# SCH_RFID-ARDUINO-FABLAB-BG-v2_2024-03-10.net
KiCad netlist of a schematic drawn in EasyEDA
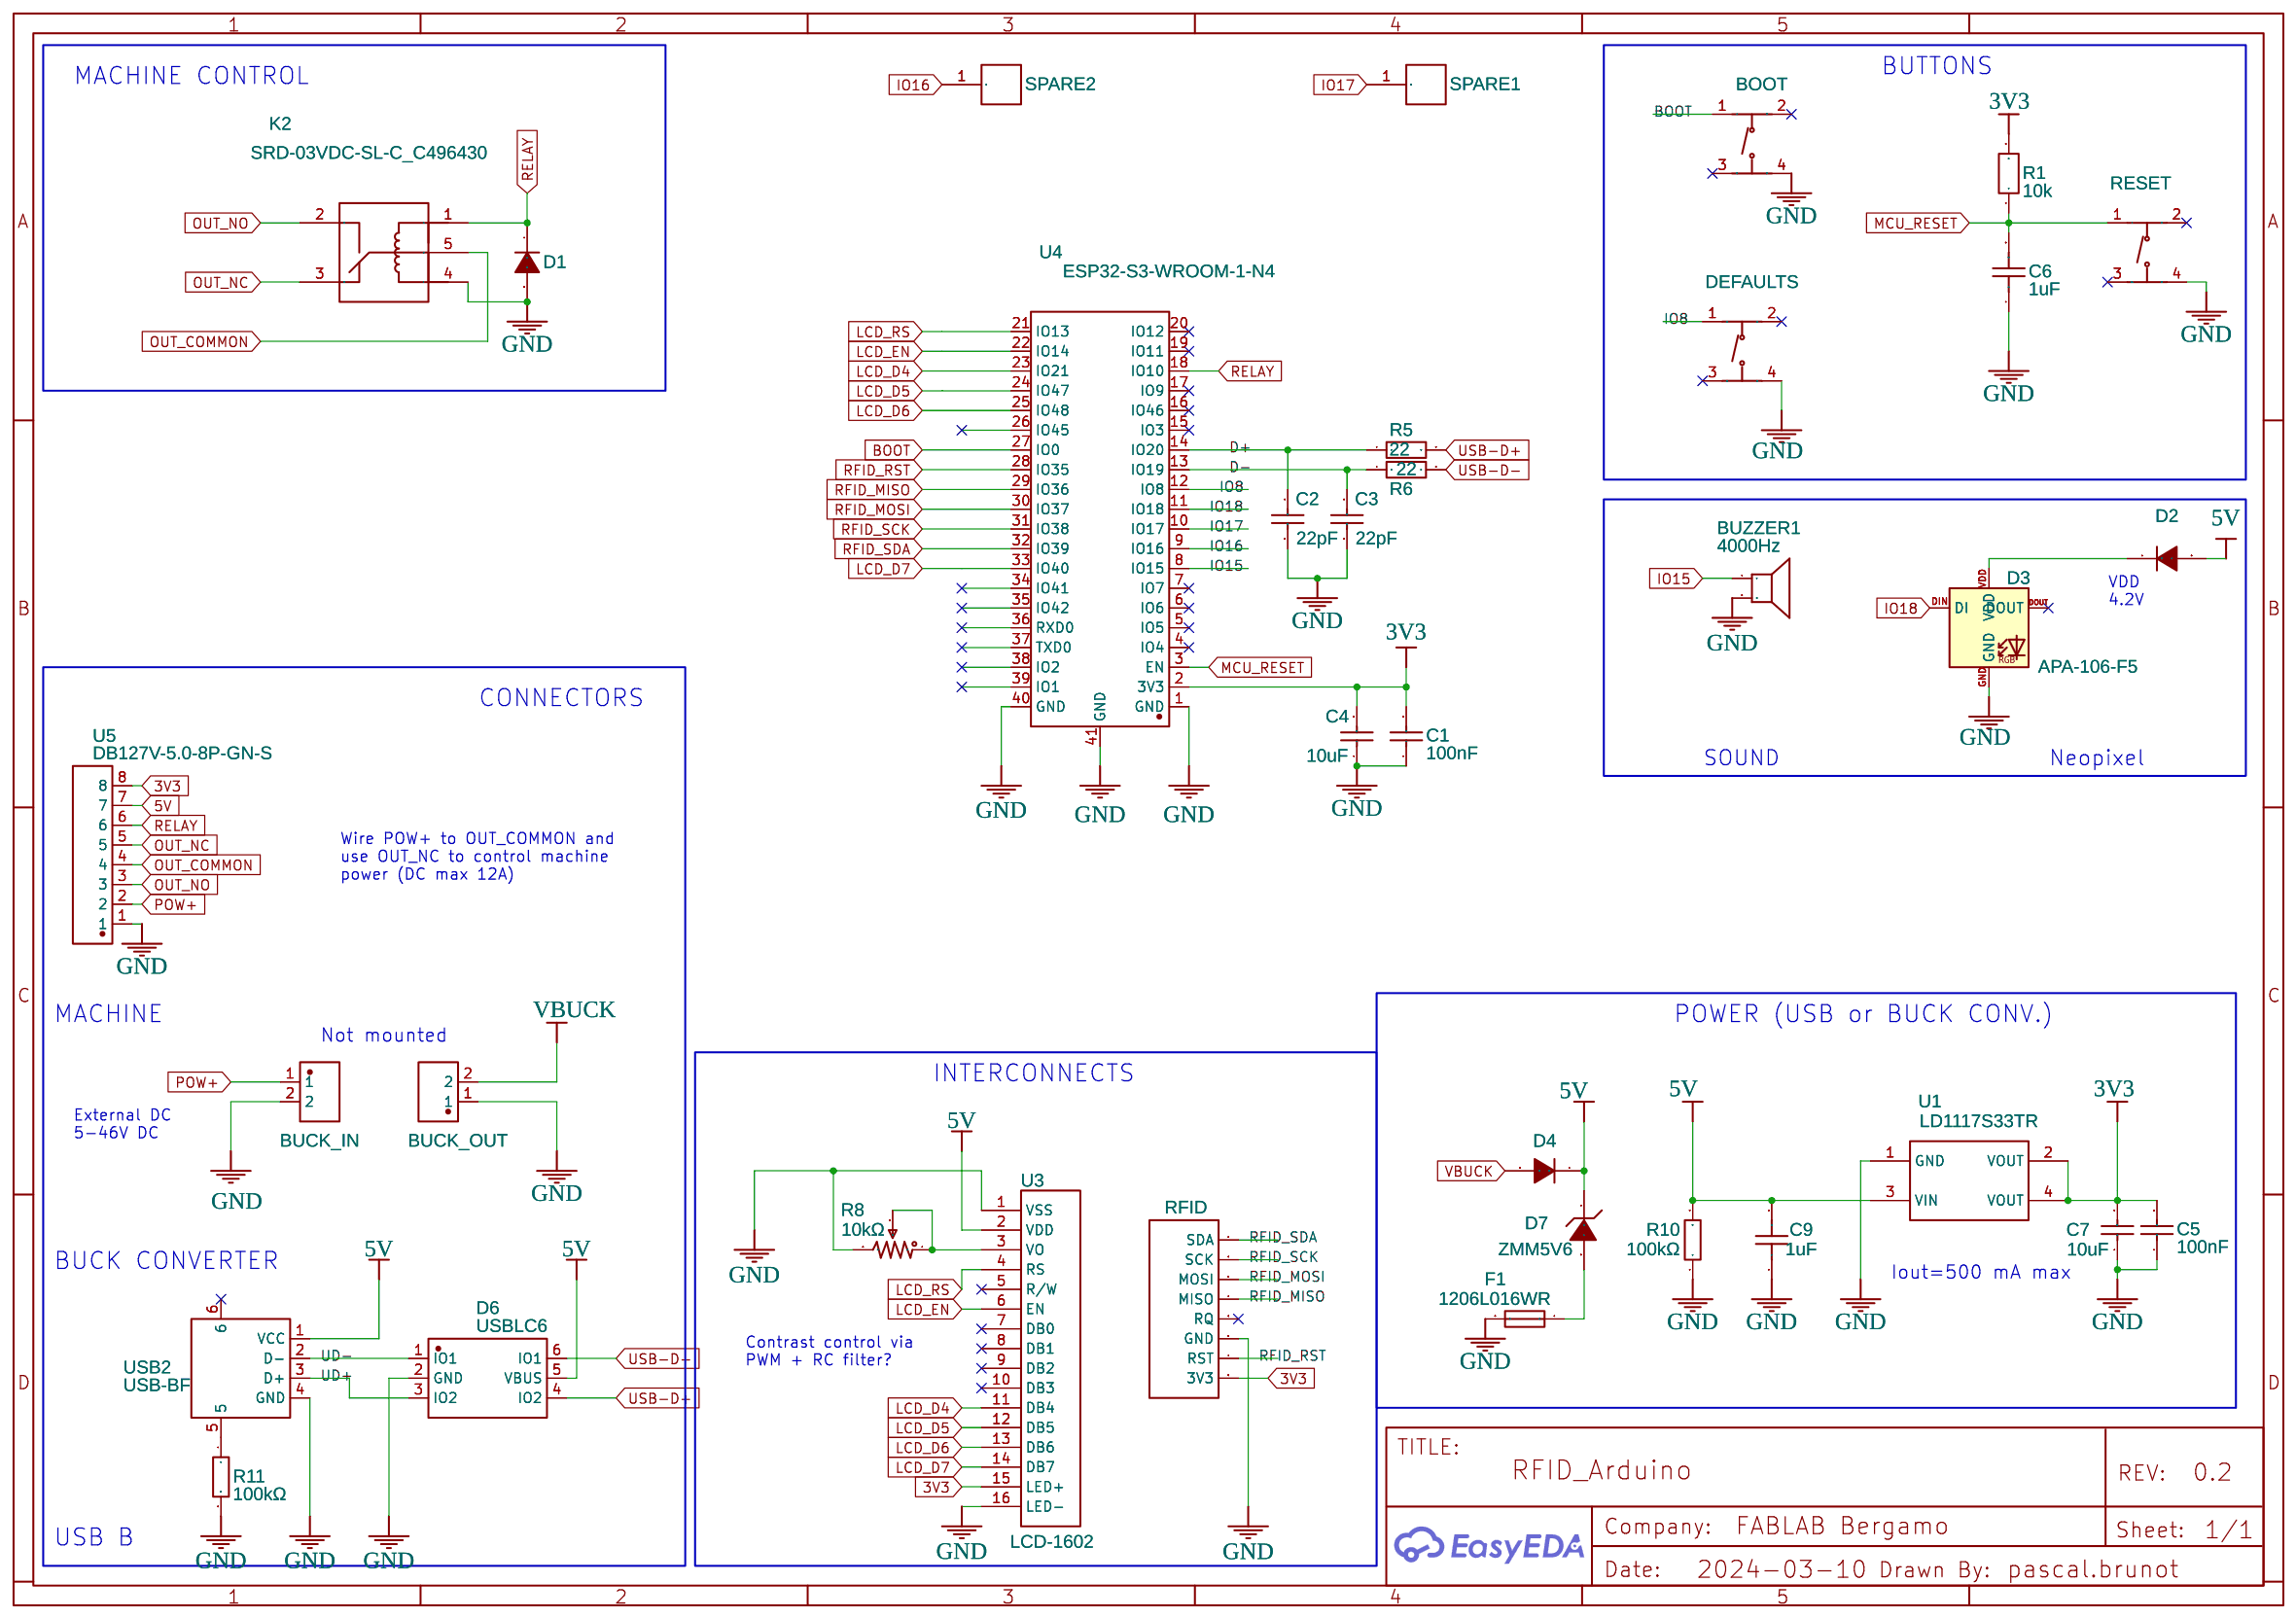
[diagram p0: schematic sheet]

(export (version "E")
  (design (tool "Eeschema 10.0.6"))
  (components
    (comp (ref "BOOT")
      (value "TS-1187A-B-A-B")
      (fields (field (name "Manufacturer") "XKB Connectivity(中国星坤)"))
      (libsource (lib "") (part "TS-1187A-B-A-B"))
    )
    (comp (ref "BUCK_IN")
      (value "KF128L-3.81-2P")
      (fields (field (name "Manufacturer") "KEFA(科发)"))
      (libsource (lib "") (part "KF128L-3.81-2P_1"))
    )
    (comp (ref "BUCK_OUT")
      (value "KF128L-3.81-2P")
      (fields (field (name "Manufacturer") "KEFA(科发)"))
      (libsource (lib "") (part "KF128L-3.81-2P"))
    )
    (comp (ref "BUZZER1")
      (value "4000Hz")
      (fields (field (name "Manufacturer Part") "SFN-12055PA6.5") (field (name "Manufacturer") "S&S(海旭)"))
      (libsource (lib "") (part "SFN-12055PA6.5"))
    )
    (comp (ref "C1")
      (value "100nF")
      (fields
        (field (name "Manufacturer Part") "CL21B104KCFNNNE")
        (field (name "Manufacturer") "SAMSUNG(三星)")
      )
      (libsource (lib "") (part "CL21B104KCFNNNE"))
    )
    (comp (ref "C2")
      (value "22pF")
      (fields (field (name "Manufacturer Part") "0402CG220J500NT") (field (name "Manufacturer") "FH(风华)"))
      (libsource (lib "") (part "0402CG220J500NT"))
    )
    (comp (ref "C3")
      (value "22pF")
      (fields (field (name "Manufacturer Part") "0402CG220J500NT") (field (name "Manufacturer") "FH(风华)"))
      (libsource (lib "") (part "0402CG220J500NT"))
    )
    (comp (ref "C4")
      (value "10uF")
      (fields
        (field (name "Manufacturer Part") "CL31A106KBHNNNE")
        (field (name "Manufacturer") "SAMSUNG(三星)")
      )
      (libsource (lib "") (part "CL31A106KBHNNNE"))
    )
    (comp (ref "C5")
      (value "100nF")
      (fields
        (field (name "Manufacturer Part") "CL21B104KCFNNNE")
        (field (name "Manufacturer") "SAMSUNG(三星)")
      )
      (libsource (lib "") (part "CL21B104KCFNNNE"))
    )
    (comp (ref "C6")
      (value "1uF")
      (fields
        (field (name "Manufacturer Part") "CL31B105KBHNNNE")
        (field (name "Manufacturer") "SAMSUNG(三星)")
      )
      (libsource (lib "") (part "CL31B105KBHNNNE"))
    )
    (comp (ref "C7")
      (value "10uF")
      (fields
        (field (name "Manufacturer Part") "CL31A106KBHNNNE")
        (field (name "Manufacturer") "SAMSUNG(三星)")
      )
      (libsource (lib "") (part "CL31A106KBHNNNE"))
    )
    (comp (ref "C9")
      (value "1uF")
      (fields
        (field (name "Manufacturer Part") "CL31B105KBHNNNE")
        (field (name "Manufacturer") "SAMSUNG(三星)")
      )
      (libsource (lib "") (part "CL31B105KBHNNNE"))
    )
    (comp (ref "D1")
      (value "SM4007PL")
      (fields (field (name "Manufacturer") "MDD"))
      (libsource (lib "") (part "SM4007PL_1"))
    )
    (comp (ref "D2")
      (value "SM4007PL")
      (fields (field (name "Manufacturer") "MDD"))
      (libsource (lib "") (part "SM4007PL"))
    )
    (comp (ref "D3") (value "APA-106-F5") (libsource (lib "") (part "APA-106-F5 COPY")))
    (comp (ref "D4")
      (value "SM4007PL")
      (fields (field (name "Manufacturer") "MDD"))
      (libsource (lib "") (part "SM4007PL_2"))
    )
    (comp (ref "D6")
      (value "USBLC6")
      (fields
        (field (name "Manufacturer Part") "USBLC6-2SC6")
        (field (name "Manufacturer") "TECH PUBLIC(台舟)")
      )
      (libsource (lib "") (part "USBLC6-2SC6_C2827654"))
    )
    (comp (ref "D7")
      (value "ZMM5V6")
      (fields (field (name "Manufacturer Part") "ZMM5V6-M") (field (name "Manufacturer") "ST(先科)"))
      (libsource (lib "") (part "ZMM5V6"))
    )
    (comp (ref "DEFAULTS")
      (value "TS-1187A-B-A-B")
      (fields (field (name "Manufacturer") "XKB Connectivity(中国星坤)"))
      (libsource (lib "") (part "TS-1187A-B-A-B_1"))
    )
    (comp (ref "F1")
      (value "1206L016WR")
      (fields (field (name "Manufacturer") "Littelfuse(美国力特)"))
      (libsource (lib "") (part "1206L016WR"))
    )
    (comp (ref "K2")
      (value "SRD-03VDC-SL-C_C496430")
      (fields (field (name "Manufacturer Part") "SRD-03VDC-SL-C") (field (name "Manufacturer") "松乐"))
      (libsource (lib "") (part "SRD-03VDC-SL-C_C496430"))
    )
    (comp (ref "P1")
      (value "RFID")
      (fields
        (field (name "Manufacturer Part") "Female headerHDR1X8-2.54")
        (field (name "Manufacturer") "BOOMELE")
      )
      (libsource (lib "") (part "RFID2"))
    )
    (comp (ref "R1")
      (value "10k")
      (fields
        (field (name "Manufacturer Part") "0805W8F1002T5E")
        (field (name "Manufacturer") "UNI-ROYAL(厚声)")
      )
      (libsource (lib "") (part "R_0603_EU"))
    )
    (comp (ref "R5")
      (value "22")
      (fields
        (field (name "Manufacturer Part") "0603WAF220JT5E")
        (field (name "Manufacturer") "UNI-ROYAL(厚声)")
      )
      (libsource (lib "") (part "0603WAF220JT5E"))
    )
    (comp (ref "R6")
      (value "22")
      (fields
        (field (name "Manufacturer Part") "0603WAF220JT5E")
        (field (name "Manufacturer") "UNI-ROYAL(厚声)")
      )
      (libsource (lib "") (part "0603WAF220JT5E"))
    )
    (comp (ref "R8")
      (value "10kΩ")
      (fields (field (name "Manufacturer Part") "TC33X-2-103E") (field (name "Manufacturer") "BOURNS"))
      (libsource (lib "") (part "TC33X-2-103E"))
    )
    (comp (ref "R10")
      (value "100kΩ")
      (fields
        (field (name "Manufacturer Part") "0805W8F1003T5E")
        (field (name "Manufacturer") "UNI-ROYAL(厚声)")
      )
      (libsource (lib "") (part "0805W8F1003T5E_C149504_1"))
    )
    (comp (ref "R11")
      (value "100kΩ")
      (fields
        (field (name "Manufacturer Part") "0805W8F1003T5E")
        (field (name "Manufacturer") "UNI-ROYAL(厚声)")
      )
      (libsource (lib "") (part "0805W8F1003T5E_C149504"))
    )
    (comp (ref "RESET")
      (value "TS-1187A-B-A-B")
      (fields (field (name "Manufacturer") "XKB Connectivity(中国星坤)"))
      (libsource (lib "") (part "TS-1187A-B-A-B_2"))
    )
    (comp (ref "SPARE1")
      (value "0577-0-43-80-21-27-10-0")
      (libsource (lib "") (part "0577-0-43-80-21-27-10-0"))
    )
    (comp (ref "SPARE2")
      (value "0577-0-43-80-21-27-10-0")
      (libsource (lib "") (part "0577-0-43-80-21-27-10-0"))
    )
    (comp (ref "U1")
      (value "LD1117S33TR")
      (fields (field (name "Manufacturer") "ST(意法半导体)"))
      (libsource (lib "") (part "LD1117S33TR"))
    )
    (comp (ref "U3")
      (value "LCD-1602")
      (fields (field (name "Manufacturer Part") "?"))
      (libsource (lib "") (part "Unknown_540_-60"))
    )
    (comp (ref "U4")
      (value "ESP32-S3-WROOM-1-N4")
      (fields (field (name "Manufacturer") "ESPRESSIF(乐鑫)"))
      (libsource (lib "") (part "ESP32-S3-WROOM-1-N4"))
    )
    (comp (ref "U5")
      (value "DB127V-5.0-8P-GN-S")
      (fields (field (name "Manufacturer") "DORABO(地博电气)"))
      (libsource (lib "") (part "DB127V-5.0-8P-GN-S"))
    )
    (comp (ref "USB2")
      (value "USB-BF")
      (fields (field (name "Manufacturer Part") "670688000") (field (name "Manufacturer") "MOLEX"))
      (libsource (lib "") (part "USB-BF"))
    )
  )
  (nets
    (net (code "1") (name "/D+") (class "Default")
      (node (ref "C2") (pin "2") (pinfunction "2_2") (pintype "input"))
      (node (ref "R5") (pin "1") (pinfunction "1_1") (pintype "input"))
      (node (ref "U4") (pin "14") (pinfunction "IO20_14") (pintype "unspecified"))
    )
    (net (code "2") (name "/D-") (class "Default")
      (node (ref "C3") (pin "2") (pinfunction "2_2") (pintype "input"))
      (node (ref "R6") (pin "1") (pinfunction "1_1") (pintype "input"))
      (node (ref "U4") (pin "13") (pinfunction "IO19_13") (pintype "unspecified"))
    )
    (net (code "3") (name "/IO8") (class "Default")
      (node (ref "DEFAULTS") (pin "1") (pinfunction "A_1") (pintype "unspecified"))
      (node (ref "U4") (pin "12") (pinfunction "IO8_12") (pintype "unspecified"))
    )
    (net (code "4") (name "/UD+") (class "Default")
      (node (ref "D6") (pin "3") (pinfunction "IO2_3") (pintype "unspecified"))
      (node (ref "USB2") (pin "3") (pinfunction "D+_3") (pintype "unspecified"))
    )
    (net (code "5") (name "/UD-") (class "Default")
      (node (ref "D6") (pin "1") (pinfunction "IO1_1") (pintype "unspecified"))
      (node (ref "USB2") (pin "2") (pinfunction "D-_2") (pintype "unspecified"))
    )
    (net (code "6") (name "3V3") (class "Default")
      (node (ref "C1") (pin "2") (pinfunction "2_2") (pintype "input"))
      (node (ref "C4") (pin "2") (pinfunction "2_2") (pintype "input"))
      (node (ref "C5") (pin "2") (pinfunction "2_2") (pintype "input"))
      (node (ref "C7") (pin "2") (pinfunction "2_2") (pintype "input"))
      (node (ref "P1") (pin "8") (pinfunction "3V3_8") (pintype "input"))
      (node (ref "R1") (pin "2") (pinfunction "2_2") (pintype "unspecified"))
      (node (ref "U1") (pin "2") (pinfunction "VOUT_2") (pintype "unspecified"))
      (node (ref "U1") (pin "4") (pinfunction "VOUT_4") (pintype "unspecified"))
      (node (ref "U3") (pin "15") (pinfunction "LED+_15") (pintype "unspecified"))
      (node (ref "U4") (pin "2") (pinfunction "3V3_2") (pintype "unspecified"))
      (node (ref "U5") (pin "8") (pinfunction "8_8") (pintype "unspecified"))
    )
    (net (code "7") (name "5V") (class "Default")
      (node (ref "C9") (pin "2") (pinfunction "2_2") (pintype "unspecified"))
      (node (ref "D2") (pin "2") (pinfunction "A_2") (pintype "unspecified"))
      (node (ref "D4") (pin "1") (pinfunction "C_1") (pintype "unspecified"))
      (node (ref "D6") (pin "5") (pinfunction "VBUS_5") (pintype "unspecified"))
      (node (ref "D7") (pin "1") (pinfunction "C_1") (pintype "unspecified"))
      (node (ref "R10") (pin "2") (pinfunction "2_2") (pintype "unspecified"))
      (node (ref "U1") (pin "3") (pinfunction "VIN_3") (pintype "unspecified"))
      (node (ref "U3") (pin "2") (pinfunction "VDD_2") (pintype "unspecified"))
      (node (ref "U5") (pin "7") (pinfunction "7_7") (pintype "unspecified"))
      (node (ref "USB2") (pin "1") (pinfunction "VCC_1") (pintype "unspecified"))
    )
    (net (code "8") (name "BOOT") (class "Default")
      (node (ref "BOOT") (pin "1") (pinfunction "A_1") (pintype "unspecified"))
      (node (ref "U4") (pin "27") (pinfunction "IO0_27") (pintype "unspecified"))
    )
    (net (code "9") (name "GND") (class "Default")
      (node (ref "BOOT") (pin "4") (pinfunction "D_4") (pintype "unspecified"))
      (node (ref "BUCK_IN") (pin "2") (pinfunction "2_2") (pintype "unspecified"))
      (node (ref "BUCK_OUT") (pin "1") (pinfunction "1_1") (pintype "unspecified"))
      (node (ref "BUZZER1") (pin "2") (pinfunction "2_2") (pintype "unspecified"))
      (node (ref "C1") (pin "1") (pinfunction "1_1") (pintype "input"))
      (node (ref "C2") (pin "1") (pinfunction "1_1") (pintype "input"))
      (node (ref "C3") (pin "1") (pinfunction "1_1") (pintype "input"))
      (node (ref "C4") (pin "1") (pinfunction "1_1") (pintype "input"))
      (node (ref "C5") (pin "1") (pinfunction "1_1") (pintype "input"))
      (node (ref "C6") (pin "1") (pinfunction "1_1") (pintype "unspecified"))
      (node (ref "C7") (pin "1") (pinfunction "1_1") (pintype "input"))
      (node (ref "C9") (pin "1") (pinfunction "1_1") (pintype "unspecified"))
      (node (ref "D1") (pin "2") (pinfunction "A_2") (pintype "unspecified"))
      (node (ref "D3") (pin "GND") (pinfunction "GND_GND") (pintype "bidirectional"))
      (node (ref "D6") (pin "2") (pinfunction "GND_2") (pintype "unspecified"))
      (node (ref "DEFAULTS") (pin "4") (pinfunction "D_4") (pintype "unspecified"))
      (node (ref "F1") (pin "2") (pinfunction "2_2") (pintype "unspecified"))
      (node (ref "K2") (pin "4") (pinfunction "4_4") (pintype "unspecified"))
      (node (ref "P1") (pin "6") (pinfunction "GND_6") (pintype "input"))
      (node (ref "R10") (pin "1") (pinfunction "1_1") (pintype "unspecified"))
      (node (ref "R11") (pin "2") (pinfunction "2_2") (pintype "unspecified"))
      (node (ref "R8") (pin "3") (pinfunction "3_3") (pintype "unspecified"))
      (node (ref "RESET") (pin "4") (pinfunction "D_4") (pintype "unspecified"))
      (node (ref "U1") (pin "1") (pinfunction "GND_1") (pintype "unspecified"))
      (node (ref "U3") (pin "1") (pinfunction "VSS_1") (pintype "unspecified"))
      (node (ref "U3") (pin "16") (pinfunction "LED-_16") (pintype "unspecified"))
      (node (ref "U4") (pin "1") (pinfunction "GND_1") (pintype "unspecified"))
      (node (ref "U4") (pin "40") (pinfunction "GND_40") (pintype "unspecified"))
      (node (ref "U4") (pin "41") (pinfunction "GND_41") (pintype "unspecified"))
      (node (ref "U5") (pin "1") (pinfunction "1_1") (pintype "unspecified"))
      (node (ref "USB2") (pin "4") (pinfunction "GND_4") (pintype "unspecified"))
    )
    (net (code "10") (name "IO15") (class "Default")
      (node (ref "BUZZER1") (pin "1") (pinfunction "1_1") (pintype "unspecified"))
      (node (ref "U4") (pin "8") (pinfunction "IO15_8") (pintype "unspecified"))
    )
    (net (code "11") (name "IO16") (class "Default")
      (node (ref "SPARE2") (pin "1") (pinfunction "1_1") (pintype "unspecified"))
      (node (ref "U4") (pin "9") (pinfunction "IO16_9") (pintype "unspecified"))
    )
    (net (code "12") (name "IO17") (class "Default")
      (node (ref "SPARE1") (pin "1") (pinfunction "1_1") (pintype "unspecified"))
      (node (ref "U4") (pin "10") (pinfunction "IO17_10") (pintype "unspecified"))
    )
    (net (code "13") (name "IO18") (class "Default")
      (node (ref "D3") (pin "DIN") (pinfunction "DI_DIN") (pintype "input"))
      (node (ref "U4") (pin "11") (pinfunction "IO18_11") (pintype "unspecified"))
    )
    (net (code "14") (name "LCD_D4") (class "Default")
      (node (ref "U3") (pin "11") (pinfunction "DB4_11") (pintype "unspecified"))
      (node (ref "U4") (pin "23") (pinfunction "IO21_23") (pintype "unspecified"))
    )
    (net (code "15") (name "LCD_D5") (class "Default")
      (node (ref "U3") (pin "12") (pinfunction "DB5_12") (pintype "unspecified"))
      (node (ref "U4") (pin "24") (pinfunction "IO47_24") (pintype "unspecified"))
    )
    (net (code "16") (name "LCD_D6") (class "Default")
      (node (ref "U3") (pin "13") (pinfunction "DB6_13") (pintype "unspecified"))
      (node (ref "U4") (pin "25") (pinfunction "IO48_25") (pintype "unspecified"))
    )
    (net (code "17") (name "LCD_D7") (class "Default")
      (node (ref "U3") (pin "14") (pinfunction "DB7_14") (pintype "unspecified"))
      (node (ref "U4") (pin "33") (pinfunction "IO40_33") (pintype "unspecified"))
    )
    (net (code "18") (name "LCD_EN") (class "Default")
      (node (ref "U3") (pin "6") (pinfunction "EN_6") (pintype "unspecified"))
      (node (ref "U4") (pin "22") (pinfunction "IO14_22") (pintype "unspecified"))
    )
    (net (code "19") (name "LCD_RS") (class "Default")
      (node (ref "U3") (pin "4") (pinfunction "RS_4") (pintype "unspecified"))
      (node (ref "U4") (pin "21") (pinfunction "IO13_21") (pintype "unspecified"))
    )
    (net (code "20") (name "MCU_RESET") (class "Default")
      (node (ref "C6") (pin "2") (pinfunction "2_2") (pintype "unspecified"))
      (node (ref "R1") (pin "1") (pinfunction "1_1") (pintype "unspecified"))
      (node (ref "RESET") (pin "1") (pinfunction "A_1") (pintype "unspecified"))
      (node (ref "U4") (pin "3") (pinfunction "EN_3") (pintype "unspecified"))
    )
    (net (code "21") (name "Net-(D2-C)") (class "Default")
      (node (ref "D2") (pin "1") (pinfunction "C_1") (pintype "unspecified"))
      (node (ref "D3") (pin "VDD") (pinfunction "VDD_VDD") (pintype "bidirectional"))
    )
    (net (code "22") (name "Net-(D7-A)") (class "Default")
      (node (ref "D7") (pin "2") (pinfunction "A_2") (pintype "unspecified"))
      (node (ref "F1") (pin "1") (pinfunction "1_1") (pintype "unspecified"))
    )
    (net (code "23") (name "Net-(R11-Pad1)") (class "Default")
      (node (ref "R11") (pin "1") (pinfunction "1_1") (pintype "unspecified"))
      (node (ref "USB2") (pin "5") (pinfunction "5_5") (pintype "unspecified"))
    )
    (net (code "24") (name "Net-(U3-VO)") (class "Default")
      (node (ref "R8") (pin "1") (pinfunction "1_1") (pintype "unspecified"))
      (node (ref "R8") (pin "2") (pinfunction "2_2") (pintype "unspecified"))
      (node (ref "U3") (pin "3") (pinfunction "VO_3") (pintype "unspecified"))
    )
    (net (code "25") (name "OUT_COMMON") (class "Default")
      (node (ref "K2") (pin "5") (pinfunction "5_5") (pintype "unspecified"))
      (node (ref "U5") (pin "4") (pinfunction "4_4") (pintype "unspecified"))
    )
    (net (code "26") (name "OUT_NC") (class "Default")
      (node (ref "K2") (pin "3") (pinfunction "3_3") (pintype "unspecified"))
      (node (ref "U5") (pin "5") (pinfunction "5_5") (pintype "unspecified"))
    )
    (net (code "27") (name "OUT_NO") (class "Default")
      (node (ref "K2") (pin "2") (pinfunction "2_2") (pintype "unspecified"))
      (node (ref "U5") (pin "3") (pinfunction "3_3") (pintype "unspecified"))
    )
    (net (code "28") (name "POW+") (class "Default")
      (node (ref "BUCK_IN") (pin "1") (pinfunction "1_1") (pintype "unspecified"))
      (node (ref "U5") (pin "2") (pinfunction "2_2") (pintype "unspecified"))
    )
    (net (code "29") (name "RELAY") (class "Default")
      (node (ref "D1") (pin "1") (pinfunction "C_1") (pintype "unspecified"))
      (node (ref "K2") (pin "1") (pinfunction "1_1") (pintype "unspecified"))
      (node (ref "U4") (pin "18") (pinfunction "IO10_18") (pintype "unspecified"))
      (node (ref "U5") (pin "6") (pinfunction "6_6") (pintype "unspecified"))
    )
    (net (code "30") (name "RFID_MISO") (class "Default")
      (node (ref "P1") (pin "4") (pinfunction "MISO_4") (pintype "input"))
      (node (ref "U4") (pin "29") (pinfunction "IO36_29") (pintype "unspecified"))
    )
    (net (code "31") (name "RFID_MOSI") (class "Default")
      (node (ref "P1") (pin "3") (pinfunction "MOSI_3") (pintype "input"))
      (node (ref "U4") (pin "30") (pinfunction "IO37_30") (pintype "unspecified"))
    )
    (net (code "32") (name "RFID_RST") (class "Default")
      (node (ref "P1") (pin "7") (pinfunction "RST_7") (pintype "input"))
      (node (ref "U4") (pin "28") (pinfunction "IO35_28") (pintype "unspecified"))
    )
    (net (code "33") (name "RFID_SCK") (class "Default")
      (node (ref "P1") (pin "2") (pinfunction "SCK_2") (pintype "input"))
      (node (ref "U4") (pin "31") (pinfunction "IO38_31") (pintype "unspecified"))
    )
    (net (code "34") (name "RFID_SDA") (class "Default")
      (node (ref "P1") (pin "1") (pinfunction "SDA_1") (pintype "input"))
      (node (ref "U4") (pin "32") (pinfunction "IO39_32") (pintype "unspecified"))
    )
    (net (code "35") (name "USB-D+") (class "Default")
      (node (ref "D6") (pin "4") (pinfunction "IO2_4") (pintype "unspecified"))
      (node (ref "R5") (pin "2") (pinfunction "2_2") (pintype "input"))
    )
    (net (code "36") (name "USB-D-") (class "Default")
      (node (ref "D6") (pin "6") (pinfunction "IO1_6") (pintype "unspecified"))
      (node (ref "R6") (pin "2") (pinfunction "2_2") (pintype "input"))
    )
    (net (code "37") (name "VBUCK") (class "Default")
      (node (ref "BUCK_OUT") (pin "2") (pinfunction "2_2") (pintype "unspecified"))
      (node (ref "D4") (pin "2") (pinfunction "A_2") (pintype "unspecified"))
    )
    (net (code "38") (name "unconnected-(BOOT-B-Pad2)") (class "Default")
      (node (ref "BOOT") (pin "2") (pinfunction "B_2") (pintype "unspecified+no_connect"))
    )
    (net (code "39") (name "unconnected-(BOOT-C-Pad3)") (class "Default")
      (node (ref "BOOT") (pin "3") (pinfunction "C_3") (pintype "unspecified+no_connect"))
    )
    (net (code "40") (name "unconnected-(D3-PadDOUT)") (class "Default")
      (node (ref "D3") (pin "DOUT") (pinfunction "DOUT_DOUT") (pintype "output+no_connect"))
    )
    (net (code "41") (name "unconnected-(DEFAULTS-B-Pad2)") (class "Default")
      (node (ref "DEFAULTS") (pin "2") (pinfunction "B_2") (pintype "unspecified+no_connect"))
    )
    (net (code "42") (name "unconnected-(DEFAULTS-C-Pad3)") (class "Default")
      (node (ref "DEFAULTS") (pin "3") (pinfunction "C_3") (pintype "unspecified+no_connect"))
    )
    (net (code "43") (name "unconnected-(P1-RQ-Pad5)") (class "Default")
      (node (ref "P1") (pin "5") (pinfunction "RQ_5") (pintype "input+no_connect"))
    )
    (net (code "44") (name "unconnected-(RESET-B-Pad2)") (class "Default")
      (node (ref "RESET") (pin "2") (pinfunction "B_2") (pintype "unspecified+no_connect"))
    )
    (net (code "45") (name "unconnected-(RESET-C-Pad3)") (class "Default")
      (node (ref "RESET") (pin "3") (pinfunction "C_3") (pintype "unspecified+no_connect"))
    )
    (net (code "46") (name "unconnected-(U3-DB0-Pad7)") (class "Default")
      (node (ref "U3") (pin "7") (pinfunction "DB0_7") (pintype "unspecified+no_connect"))
    )
    (net (code "47") (name "unconnected-(U3-DB1-Pad8)") (class "Default")
      (node (ref "U3") (pin "8") (pinfunction "DB1_8") (pintype "unspecified+no_connect"))
    )
    (net (code "48") (name "unconnected-(U3-DB2-Pad9)") (class "Default")
      (node (ref "U3") (pin "9") (pinfunction "DB2_9") (pintype "unspecified+no_connect"))
    )
    (net (code "49") (name "unconnected-(U3-DB3-Pad10)") (class "Default")
      (node (ref "U3") (pin "10") (pinfunction "DB3_10") (pintype "unspecified+no_connect"))
    )
    (net (code "50") (name "unconnected-(U3-R{slash}W-Pad5)") (class "Default")
      (node (ref "U3") (pin "5") (pinfunction "R/W_5") (pintype "unspecified+no_connect"))
    )
    (net (code "51") (name "unconnected-(U4-IO1-Pad39)") (class "Default")
      (node (ref "U4") (pin "39") (pinfunction "IO1_39") (pintype "unspecified+no_connect"))
    )
    (net (code "52") (name "unconnected-(U4-IO2-Pad38)") (class "Default")
      (node (ref "U4") (pin "38") (pinfunction "IO2_38") (pintype "unspecified+no_connect"))
    )
    (net (code "53") (name "unconnected-(U4-IO3-Pad15)") (class "Default")
      (node (ref "U4") (pin "15") (pinfunction "IO3_15") (pintype "unspecified+no_connect"))
    )
    (net (code "54") (name "unconnected-(U4-IO4-Pad4)") (class "Default")
      (node (ref "U4") (pin "4") (pinfunction "IO4_4") (pintype "unspecified+no_connect"))
    )
    (net (code "55") (name "unconnected-(U4-IO5-Pad5)") (class "Default")
      (node (ref "U4") (pin "5") (pinfunction "IO5_5") (pintype "unspecified+no_connect"))
    )
    (net (code "56") (name "unconnected-(U4-IO6-Pad6)") (class "Default")
      (node (ref "U4") (pin "6") (pinfunction "IO6_6") (pintype "unspecified+no_connect"))
    )
    (net (code "57") (name "unconnected-(U4-IO7-Pad7)") (class "Default")
      (node (ref "U4") (pin "7") (pinfunction "IO7_7") (pintype "unspecified+no_connect"))
    )
    (net (code "58") (name "unconnected-(U4-IO9-Pad17)") (class "Default")
      (node (ref "U4") (pin "17") (pinfunction "IO9_17") (pintype "unspecified+no_connect"))
    )
    (net (code "59") (name "unconnected-(U4-IO11-Pad19)") (class "Default")
      (node (ref "U4") (pin "19") (pinfunction "IO11_19") (pintype "unspecified+no_connect"))
    )
    (net (code "60") (name "unconnected-(U4-IO12-Pad20)") (class "Default")
      (node (ref "U4") (pin "20") (pinfunction "IO12_20") (pintype "unspecified+no_connect"))
    )
    (net (code "61") (name "unconnected-(U4-IO41-Pad34)") (class "Default")
      (node (ref "U4") (pin "34") (pinfunction "IO41_34") (pintype "unspecified+no_connect"))
    )
    (net (code "62") (name "unconnected-(U4-IO42-Pad35)") (class "Default")
      (node (ref "U4") (pin "35") (pinfunction "IO42_35") (pintype "unspecified+no_connect"))
    )
    (net (code "63") (name "unconnected-(U4-IO45-Pad26)") (class "Default")
      (node (ref "U4") (pin "26") (pinfunction "IO45_26") (pintype "unspecified+no_connect"))
    )
    (net (code "64") (name "unconnected-(U4-IO46-Pad16)") (class "Default")
      (node (ref "U4") (pin "16") (pinfunction "IO46_16") (pintype "unspecified+no_connect"))
    )
    (net (code "65") (name "unconnected-(U4-RXD0-Pad36)") (class "Default")
      (node (ref "U4") (pin "36") (pinfunction "RXD0_36") (pintype "unspecified+no_connect"))
    )
    (net (code "66") (name "unconnected-(U4-TXD0-Pad37)") (class "Default")
      (node (ref "U4") (pin "37") (pinfunction "TXD0_37") (pintype "unspecified+no_connect"))
    )
    (net (code "67") (name "unconnected-(USB2-Pad6)") (class "Default")
      (node (ref "USB2") (pin "6") (pinfunction "6_6") (pintype "unspecified+no_connect"))
    )
  )
)
